# DWM3000.net
KiCad netlist of a schematic drawn in Altium Designer
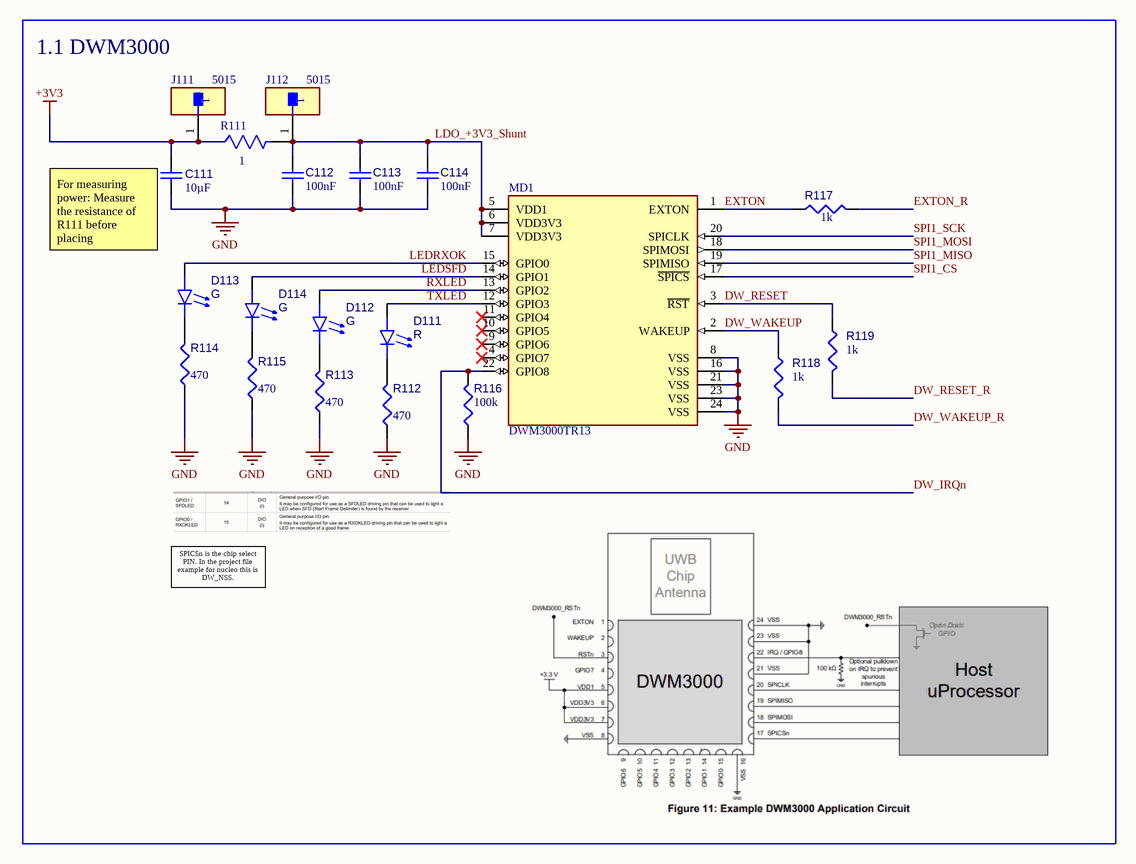
[diagram p0: DWM3000.SchDoc]

(export (version "E")
  (design (tool "Eeschema 10.0.6"))
  (components
    (comp (ref "C111")
      (value "10µF")
      (footprint "CAPC0603(1608)100_L")
      (description "Chip Capacitor, 10µF +/-20%, 10V, 0603, Thickness 1 mm")
      (fields (field (name "TOLERANCE") "10%") (field (name "Comment") "Capacitor 10µF +/-20% 10V 0603"))
      (libsource (lib "University of British Columbia") (part "CAP-NP-2"))
    )
    (comp (ref "C112")
      (value "100nF")
      (footprint "CAPC0402(1005)60_L")
      (description "Chip Capacitor, 100nF +/-20%, 10V, 0402, Thickness 0.6 mm")
      (fields (field (name "TOLERANCE") "20%") (field (name "Comment") "Capacitor 100nF +/-20% 10V 0402"))
      (libsource (lib "University of British Columbia") (part "CAP-NP-2"))
    )
    (comp (ref "C113")
      (value "100nF")
      (footprint "CAPC0402(1005)60_L")
      (description "Chip Capacitor, 100nF +/-20%, 10V, 0402, Thickness 0.6 mm")
      (fields (field (name "TOLERANCE") "20%") (field (name "Comment") "Capacitor 100nF +/-20% 10V 0402"))
      (libsource (lib "University of British Columbia") (part "CAP-NP-2"))
    )
    (comp (ref "C114")
      (value "100nF")
      (footprint "CAPC0402(1005)60_L")
      (description "Chip Capacitor, 100nF +/-20%, 10V, 0402, Thickness 0.6 mm")
      (fields (field (name "TOLERANCE") "20%") (field (name "Comment") "Capacitor 100nF +/-20% 10V 0402"))
      (libsource (lib "University of British Columbia") (part "CAP-NP-2"))
    )
    (comp (ref "D111")
      (value "R")
      (footprint "WL-SMCW_0603_150060xx75000")
      (description "Single Color LED, Red, Water Clear, 1.1mm")
      (libsource (lib "University of British Columbia") (part "DIODE-LED-2"))
    )
    (comp (ref "D112")
      (value "G")
      (footprint "WL-SMCW_0603_150060xx75000")
      (description "Single Color LED, Green, Water Clear, 1.1mm")
      (libsource (lib "University of British Columbia") (part "DIODE-LED-2"))
    )
    (comp (ref "D113")
      (value "G")
      (footprint "WL-SMCW_0603_150060xx75000")
      (description "Single Color LED, Green, Water Clear, 1.1mm")
      (libsource (lib "University of British Columbia") (part "DIODE-LED-2"))
    )
    (comp (ref "D114")
      (value "G")
      (footprint "WL-SMCW_0603_150060xx75000")
      (description "Single Color LED, Green, Water Clear, 1.1mm")
      (libsource (lib "University of British Columbia") (part "DIODE-LED-2"))
    )
    (comp (ref "J111")
      (value "5015")
      (footprint "FP-5015-MFG")
      (description "Interconnection Device")
      (libsource (lib "University of British Columbia") (part "dd45045ce8184df9e99e12baf3f412c"))
    )
    (comp (ref "J112")
      (value "5015")
      (footprint "FP-5015-MFG")
      (description "Interconnection Device")
      (libsource (lib "University of British Columbia") (part "dd45045ce8184df9e99e12baf3f412c"))
    )
    (comp (ref "MD1")
      (value "DWM3000TR13")
      (footprint "FP-DWM3000TR13-MFG")
      (description "UWB Transceiver Module")
      (libsource (lib "University of British Columbia") (part "094cfe914922597e69cd10df7811a9c"))
    )
    (comp (ref "R111")
      (value "1")
      (footprint "FP-CRCW0603-HPe3-MFG")
      (fields
        (field (name "TOLERANCE") "1%")
        (field (name "POWER") "250mW")
        (field (name "Comment") "CRCW06031R00FKEAHP")
      )
      (libsource (lib "University of British Columbia") (part "1029c3af85768c4190bb7ad29bc67b5"))
    )
    (comp (ref "R112")
      (value "470")
      (footprint "RESC0805(2012)_L")
      (description "Chip Resistor, 470 Ohms, +/-5%, 125 mW, -55 to 155 degC, 0805")
      (fields (field (name "TOLERANCE") "5%") (field (name "POWER") "125mW"))
      (libsource (lib "University of British Columbia") (part "RES-2"))
    )
    (comp (ref "R113")
      (value "470")
      (footprint "RESC0805(2012)_L")
      (description "Chip Resistor, 470 Ohms, +/-5%, 125 mW, -55 to 155 degC, 0805")
      (fields (field (name "TOLERANCE") "5%") (field (name "POWER") "125mW"))
      (libsource (lib "University of British Columbia") (part "RES-2"))
    )
    (comp (ref "R114")
      (value "470")
      (footprint "RESC0805(2012)_L")
      (description "Chip Resistor, 470 Ohms, +/-5%, 125 mW, -55 to 155 degC, 0805")
      (fields (field (name "TOLERANCE") "5%") (field (name "POWER") "125mW"))
      (libsource (lib "University of British Columbia") (part "RES-2"))
    )
    (comp (ref "R115")
      (value "470")
      (footprint "RESC0805(2012)_L")
      (description "Chip Resistor, 470 Ohms, +/-5%, 125 mW, -55 to 155 degC, 0805")
      (fields (field (name "TOLERANCE") "5%") (field (name "POWER") "125mW"))
      (libsource (lib "University of British Columbia") (part "RES-2"))
    )
    (comp (ref "R116")
      (value "100k")
      (footprint "RESC1608X55X25ML10T15")
      (description "Chip Resistor, 100 KOhm, +/- 1%, 0.1 W, -55 to 155 degC, 0603 (1608 Metric)")
      (fields (field (name "TOLERANCE") "1%") (field (name "POWER") "100mW"))
      (libsource (lib "University of British Columbia") (part "RES-2"))
    )
    (comp (ref "R117")
      (value "1k")
      (footprint "RESC1005X40X25ML10T10")
      (description "Chip Resistor, 1 KOhm, +/- 5%, 0.063 W, -55 to 155 degC, 0402 (1005 Metric)")
      (fields (field (name "TOLERANCE") "5%") (field (name "POWER") "63mW"))
      (libsource (lib "University of British Columbia") (part "RES-2"))
    )
    (comp (ref "R118")
      (value "1k")
      (footprint "RESC1005X40X25ML10T10")
      (description "Chip Resistor, 1 KOhm, +/- 5%, 0.063 W, -55 to 155 degC, 0402 (1005 Metric)")
      (fields (field (name "TOLERANCE") "5%") (field (name "POWER") "63mW"))
      (libsource (lib "University of British Columbia") (part "RES-2"))
    )
    (comp (ref "R119")
      (value "1k")
      (footprint "RESC1005X40X25ML10T10")
      (description "Chip Resistor, 1 KOhm, +/- 5%, 0.063 W, -55 to 155 degC, 0402 (1005 Metric)")
      (fields (field (name "TOLERANCE") "5%") (field (name "POWER") "63mW"))
      (libsource (lib "University of British Columbia") (part "RES-2"))
    )
  )
  (nets
    (net (code "1") (name "+3V3") (class "Default")
      (node (ref "C111") (pin "1") (pinfunction "1_1") (pintype "passive"))
      (node (ref "J111") (pin "1") (pinfunction "1_1") (pintype "passive"))
      (node (ref "R111") (pin "1") (pinfunction "1_1") (pintype "passive"))
    )
    (net (code "2") (name "/DW_IRQn") (class "Default")
      (node (ref "MD1") (pin "22") (pinfunction "GPIO8_22") (pintype "bidirectional"))
      (node (ref "R116") (pin "2") (pinfunction "2_2") (pintype "passive"))
    )
    (net (code "3") (name "/DW_RESET") (class "Default")
      (node (ref "MD1") (pin "3") (pinfunction "~{RST}_3") (pintype "input"))
      (node (ref "R119") (pin "1") (pinfunction "1_1") (pintype "passive"))
    )
    (net (code "4") (name "/DW_RESET_R") (class "Default")
      (node (ref "R119") (pin "2") (pinfunction "2_2") (pintype "passive"))
    )
    (net (code "5") (name "/DW_WAKEUP") (class "Default")
      (node (ref "MD1") (pin "2") (pinfunction "WAKEUP_2") (pintype "input"))
      (node (ref "R118") (pin "1") (pinfunction "1_1") (pintype "passive"))
    )
    (net (code "6") (name "/DW_WAKEUP_R") (class "Default")
      (node (ref "R118") (pin "2") (pinfunction "2_2") (pintype "passive"))
    )
    (net (code "7") (name "/EXTON") (class "Default")
      (node (ref "MD1") (pin "1") (pinfunction "EXTON_1") (pintype "passive"))
      (node (ref "R117") (pin "1") (pinfunction "1_1") (pintype "passive"))
    )
    (net (code "8") (name "/EXTON_R") (class "Default")
      (node (ref "R117") (pin "2") (pinfunction "2_2") (pintype "passive"))
    )
    (net (code "9") (name "/LDO_+3V3_Shunt") (class "Default")
      (node (ref "C112") (pin "2") (pinfunction "2_2") (pintype "passive"))
      (node (ref "C113") (pin "2") (pinfunction "2_2") (pintype "passive"))
      (node (ref "C114") (pin "2") (pinfunction "2_2") (pintype "passive"))
      (node (ref "J112") (pin "1") (pinfunction "1_1") (pintype "passive"))
      (node (ref "MD1") (pin "5") (pinfunction "VDD1_5") (pintype "power_in"))
      (node (ref "MD1") (pin "6") (pinfunction "VDD3V3_6") (pintype "power_in"))
      (node (ref "MD1") (pin "7") (pinfunction "VDD3V3_7") (pintype "power_in"))
      (node (ref "R111") (pin "2") (pinfunction "2_2") (pintype "passive"))
    )
    (net (code "10") (name "/LEDRXOK") (class "Default")
      (node (ref "D113") (pin "2") (pinfunction "A_2") (pintype "passive"))
      (node (ref "MD1") (pin "15") (pinfunction "GPIO0_15") (pintype "bidirectional"))
    )
    (net (code "11") (name "/LEDSFD") (class "Default")
      (node (ref "D114") (pin "2") (pinfunction "A_2") (pintype "passive"))
      (node (ref "MD1") (pin "14") (pinfunction "GPIO1_14") (pintype "bidirectional"))
    )
    (net (code "12") (name "/RXLED") (class "Default")
      (node (ref "D112") (pin "2") (pinfunction "A_2") (pintype "passive"))
      (node (ref "MD1") (pin "13") (pinfunction "GPIO2_13") (pintype "bidirectional"))
    )
    (net (code "13") (name "/SPI1_CS") (class "Default")
      (node (ref "MD1") (pin "17") (pinfunction "~{SPICS}_17") (pintype "input"))
    )
    (net (code "14") (name "/SPI1_MISO") (class "Default")
      (node (ref "MD1") (pin "19") (pinfunction "SPIMISO_19") (pintype "input"))
    )
    (net (code "15") (name "/SPI1_MOSI") (class "Default")
      (node (ref "MD1") (pin "18") (pinfunction "SPIMOSI_18") (pintype "output"))
    )
    (net (code "16") (name "/SPI1_SCK") (class "Default")
      (node (ref "MD1") (pin "20") (pinfunction "SPICLK_20") (pintype "input"))
    )
    (net (code "17") (name "/TXLED") (class "Default")
      (node (ref "D111") (pin "2") (pinfunction "A_2") (pintype "passive"))
      (node (ref "MD1") (pin "12") (pinfunction "GPIO3_12") (pintype "bidirectional"))
    )
    (net (code "18") (name "GND") (class "Default")
      (node (ref "C111") (pin "2") (pinfunction "2_2") (pintype "passive"))
      (node (ref "C112") (pin "1") (pinfunction "1_1") (pintype "passive"))
      (node (ref "C113") (pin "1") (pinfunction "1_1") (pintype "passive"))
      (node (ref "C114") (pin "1") (pinfunction "1_1") (pintype "passive"))
      (node (ref "MD1") (pin "16") (pinfunction "VSS_16") (pintype "power_in"))
      (node (ref "MD1") (pin "21") (pinfunction "VSS_21") (pintype "power_in"))
      (node (ref "MD1") (pin "23") (pinfunction "VSS_23") (pintype "power_in"))
      (node (ref "MD1") (pin "24") (pinfunction "VSS_24") (pintype "power_in"))
      (node (ref "MD1") (pin "8") (pinfunction "VSS_8") (pintype "power_in"))
      (node (ref "R112") (pin "1") (pinfunction "1_1") (pintype "passive"))
      (node (ref "R113") (pin "1") (pinfunction "1_1") (pintype "passive"))
      (node (ref "R114") (pin "1") (pinfunction "1_1") (pintype "passive"))
      (node (ref "R115") (pin "1") (pinfunction "1_1") (pintype "passive"))
      (node (ref "R116") (pin "1") (pinfunction "1_1") (pintype "passive"))
    )
    (net (code "19") (name "Net-(D111-K)") (class "Default")
      (node (ref "D111") (pin "1") (pinfunction "K_1") (pintype "passive"))
      (node (ref "R112") (pin "2") (pinfunction "2_2") (pintype "passive"))
    )
    (net (code "20") (name "Net-(D112-K)") (class "Default")
      (node (ref "D112") (pin "1") (pinfunction "K_1") (pintype "passive"))
      (node (ref "R113") (pin "2") (pinfunction "2_2") (pintype "passive"))
    )
    (net (code "21") (name "Net-(D113-K)") (class "Default")
      (node (ref "D113") (pin "1") (pinfunction "K_1") (pintype "passive"))
      (node (ref "R114") (pin "2") (pinfunction "2_2") (pintype "passive"))
    )
    (net (code "22") (name "Net-(D114-K)") (class "Default")
      (node (ref "D114") (pin "1") (pinfunction "K_1") (pintype "passive"))
      (node (ref "R115") (pin "2") (pinfunction "2_2") (pintype "passive"))
    )
    (net (code "23") (name "unconnected-(MD1-GPIO4-Pad11)") (class "Default")
      (node (ref "MD1") (pin "11") (pinfunction "GPIO4_11") (pintype "bidirectional+no_connect"))
    )
    (net (code "24") (name "unconnected-(MD1-GPIO5-Pad10)") (class "Default")
      (node (ref "MD1") (pin "10") (pinfunction "GPIO5_10") (pintype "bidirectional+no_connect"))
    )
    (net (code "25") (name "unconnected-(MD1-GPIO6-Pad9)") (class "Default")
      (node (ref "MD1") (pin "9") (pinfunction "GPIO6_9") (pintype "bidirectional+no_connect"))
    )
    (net (code "26") (name "unconnected-(MD1-GPIO7-Pad4)") (class "Default")
      (node (ref "MD1") (pin "4") (pinfunction "GPIO7_4") (pintype "bidirectional+no_connect"))
    )
  )
)
